# DWM1000Breakout.net
KiCad netlist of a schematic drawn in Altium Designer
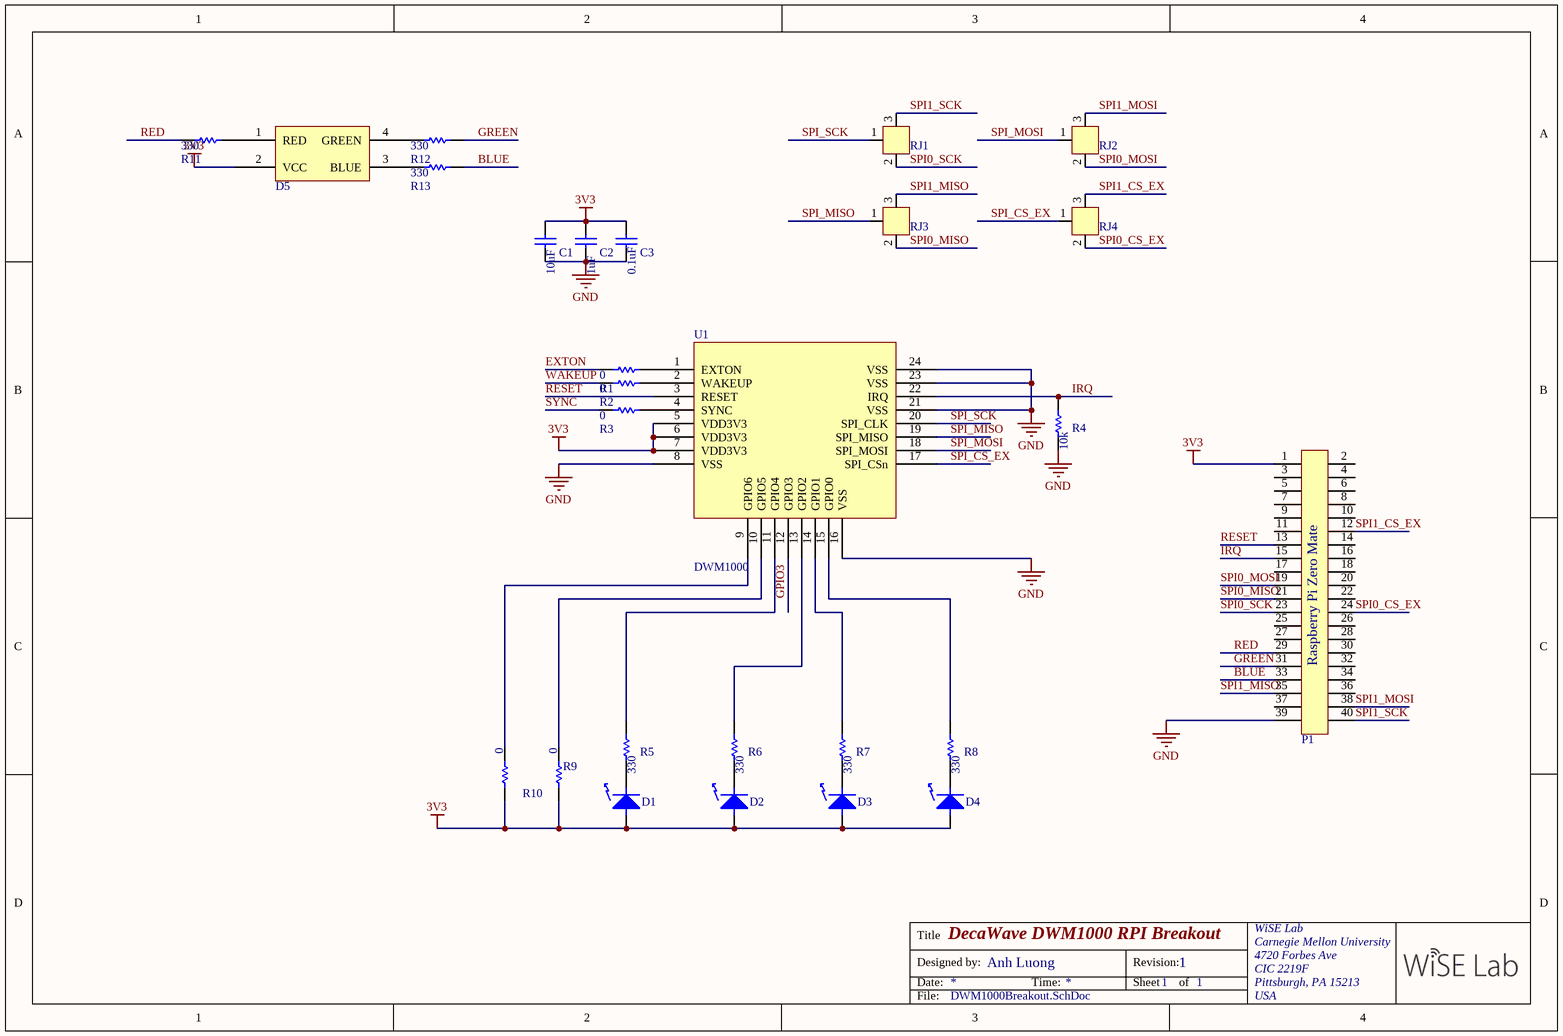
[diagram p0: DWM1000Breakout.SchDoc]

(export (version "E")
  (design (tool "Eeschema 10.0.6"))
  (components
    (comp (ref "C1")
      (value "GRM188R60J106ME47D")
      (footprint "CAPC1608X08N (0603)")
      (description "CAP CER 10UF 6.3V 20% X5R 0603")
      (fields
        (field (name "MANUFACTURER") "Murata Electronics North America")
        (field (name "TOLERANCE") "±20%")
      )
      (libsource (lib "DWM1000Breakout") (part "GRM188R60J106ME47D"))
    )
    (comp (ref "C2")
      (value "GRM188R61A105KA61D")
      (footprint "CAPC1608X08N (0603)")
      (description "CAP CER 1UF 10V 10% X5R 0603")
      (fields
        (field (name "MANUFACTURER") "Murata Electronics North America")
        (field (name "TOLERANCE") "±10%")
      )
      (libsource (lib "DWM1000Breakout") (part "GRM188R61A105KA61D"))
    )
    (comp (ref "C3")
      (value "GRM188R71C104KA01D")
      (footprint "CAPC1608X08N (0603)")
      (description "CAP CER 0.1UF 16V 10% X7R 0603")
      (fields
        (field (name "MANUFACTURER") "Murata Electronics North America")
        (field (name "TOLERANCE") "±10%")
      )
      (libsource (lib "DWM1000Breakout") (part "GRM188R71C104KA01D"))
    )
    (comp (ref "D1")
      (value "LG Q971-KN-1")
      (footprint "CHIPLED0603")
      (description "LED CHIPLED 570NM GREEN 0603 SMD")
      (fields (field (name "MANUFACTURER") "OSRAM Opto Semiconductors Inc"))
      (libsource (lib "DWM1000Breakout") (part "LG Q971-KN-1"))
    )
    (comp (ref "D2")
      (value "LG Q971-KN-1")
      (footprint "CHIPLED0603")
      (description "LED CHIPLED 570NM GREEN 0603 SMD")
      (fields (field (name "MANUFACTURER") "OSRAM Opto Semiconductors Inc"))
      (libsource (lib "DWM1000Breakout") (part "LG Q971-KN-1"))
    )
    (comp (ref "D3")
      (value "LG Q971-KN-1")
      (footprint "CHIPLED0603")
      (description "LED CHIPLED 570NM GREEN 0603 SMD")
      (fields (field (name "MANUFACTURER") "OSRAM Opto Semiconductors Inc"))
      (libsource (lib "DWM1000Breakout") (part "LG Q971-KN-1"))
    )
    (comp (ref "D4")
      (value "LG Q971-KN-1")
      (footprint "CHIPLED0603")
      (description "LED CHIPLED 570NM GREEN 0603 SMD")
      (fields (field (name "MANUFACTURER") "OSRAM Opto Semiconductors Inc"))
      (libsource (lib "DWM1000Breakout") (part "LG Q971-KN-1"))
    )
    (comp (ref "D5")
      (value "CLV1A-FKB-CJ1M1F1BB7R4S3")
      (footprint "CREE LV1")
      (description "LED RED/GREEN/BLUE PLCC4 SMD")
      (fields (field (name "MANUFACTURER") "Cree Inc"))
      (libsource (lib "Passives") (part "CLV1A-FKB-CJ1M1F1BB7R4S3"))
    )
    (comp (ref "P1")
      (value "Raspbery Pi Zero Mate")
      (footprint "Raspberry Pi Zero")
      (description "The header and mechanical drawings for connnecting a Raspbery Pi Zero")
      (libsource (lib "Connectors") (part "Raspberry Pi Zero Mate"))
    )
    (comp (ref "R1")
      (value "MCR03ERTJ000")
      (footprint "RESC1608X06N (0603)")
      (description "RES 0.0 OHM 1/10W JUMP 0603 SMD")
      (fields (field (name "MANUFACTURER") "Rohm Semiconductor") (field (name "TOLERANCE") "Jumper"))
      (libsource (lib "DWM1000Breakout") (part "MCR03ERTJ000"))
    )
    (comp (ref "R2")
      (value "MCR03ERTJ000")
      (footprint "RESC1608X06N (0603)")
      (description "RES 0.0 OHM 1/10W JUMP 0603 SMD")
      (fields (field (name "MANUFACTURER") "Rohm Semiconductor") (field (name "TOLERANCE") "Jumper"))
      (libsource (lib "DWM1000Breakout") (part "MCR03ERTJ000"))
    )
    (comp (ref "R3")
      (value "MCR03ERTJ000")
      (footprint "RESC1608X06N (0603)")
      (description "RES 0.0 OHM 1/10W JUMP 0603 SMD")
      (fields (field (name "MANUFACTURER") "Rohm Semiconductor") (field (name "TOLERANCE") "Jumper"))
      (libsource (lib "DWM1000Breakout") (part "MCR03ERTJ000"))
    )
    (comp (ref "R4")
      (value "MCR03ERTJ103")
      (footprint "RESC1608X06N (0603)")
      (description "RES 10K OHM 1/10W 5% 0603 SMD")
      (fields (field (name "MANUFACTURER") "Rohm Semiconductor") (field (name "TOLERANCE") "±5%"))
      (libsource (lib "DWM1000Breakout") (part "MCR03ERTJ103"))
    )
    (comp (ref "R5")
      (value "MCR03ERTJ331")
      (footprint "RESC1608X06N (0603)")
      (description "RES 330 OHM 1/10W 5% 0603 SMD")
      (fields (field (name "MANUFACTURER") "Rohm Semiconductor") (field (name "TOLERANCE") "±5%"))
      (libsource (lib "Passives") (part "MCR03ERTJ331"))
    )
    (comp (ref "R6")
      (value "MCR03ERTJ331")
      (footprint "RESC1608X06N (0603)")
      (description "RES 330 OHM 1/10W 5% 0603 SMD")
      (fields (field (name "MANUFACTURER") "Rohm Semiconductor") (field (name "TOLERANCE") "±5%"))
      (libsource (lib "Passives") (part "MCR03ERTJ331"))
    )
    (comp (ref "R7")
      (value "MCR03ERTJ331")
      (footprint "RESC1608X06N (0603)")
      (description "RES 330 OHM 1/10W 5% 0603 SMD")
      (fields (field (name "MANUFACTURER") "Rohm Semiconductor") (field (name "TOLERANCE") "±5%"))
      (libsource (lib "Passives") (part "MCR03ERTJ331"))
    )
    (comp (ref "R8")
      (value "MCR03ERTJ331")
      (footprint "RESC1608X06N (0603)")
      (description "RES 330 OHM 1/10W 5% 0603 SMD")
      (fields (field (name "MANUFACTURER") "Rohm Semiconductor") (field (name "TOLERANCE") "±5%"))
      (libsource (lib "Passives") (part "MCR03ERTJ331"))
    )
    (comp (ref "R9")
      (value "MCR03ERTJ000")
      (footprint "RESC1608X06N (0603)")
      (description "RES 0.0 OHM 1/10W JUMP 0603 SMD")
      (fields (field (name "MANUFACTURER") "Rohm Semiconductor") (field (name "TOLERANCE") "Jumper"))
      (libsource (lib "DWM1000Breakout") (part "MCR03ERTJ000"))
    )
    (comp (ref "R10")
      (value "MCR03ERTJ000")
      (footprint "RESC1608X06N (0603)")
      (description "RES 0.0 OHM 1/10W JUMP 0603 SMD")
      (fields (field (name "MANUFACTURER") "Rohm Semiconductor") (field (name "TOLERANCE") "Jumper"))
      (libsource (lib "DWM1000Breakout") (part "MCR03ERTJ000"))
    )
    (comp (ref "R11")
      (value "MCR03ERTJ331")
      (footprint "RESC1608X06N (0603)")
      (description "RES 330 OHM 1/10W 5% 0603 SMD")
      (fields (field (name "MANUFACTURER") "Rohm Semiconductor") (field (name "TOLERANCE") "±5%"))
      (libsource (lib "Passives") (part "MCR03ERTJ331"))
    )
    (comp (ref "R12")
      (value "MCR03ERTJ331")
      (footprint "RESC1608X06N (0603)")
      (description "RES 330 OHM 1/10W 5% 0603 SMD")
      (fields (field (name "MANUFACTURER") "Rohm Semiconductor") (field (name "TOLERANCE") "±5%"))
      (libsource (lib "Passives") (part "MCR03ERTJ331"))
    )
    (comp (ref "R13")
      (value "MCR03ERTJ331")
      (footprint "RESC1608X06N (0603)")
      (description "RES 330 OHM 1/10W 5% 0603 SMD")
      (fields (field (name "MANUFACTURER") "Rohm Semiconductor") (field (name "TOLERANCE") "±5%"))
      (libsource (lib "Passives") (part "MCR03ERTJ331"))
    )
    (comp (ref "RJ1")
      (value "R_J")
      (footprint "RJ")
      (description "Resistor Jumper")
      (libsource (lib "DWM1000Breakout") (part "R_J"))
    )
    (comp (ref "RJ2")
      (value "R_J")
      (footprint "RJ")
      (description "Resistor Jumper")
      (libsource (lib "DWM1000Breakout") (part "R_J"))
    )
    (comp (ref "RJ3")
      (value "R_J")
      (footprint "RJ")
      (description "Resistor Jumper")
      (libsource (lib "DWM1000Breakout") (part "R_J"))
    )
    (comp (ref "RJ4")
      (value "R_J")
      (footprint "RJ")
      (description "Resistor Jumper")
      (libsource (lib "DWM1000Breakout") (part "R_J"))
    )
    (comp (ref "U1")
      (value "DWM1000")
      (footprint "DWM1000")
      (description "MOD IEEE802.15.4-2011 UWB TXRX")
      (fields (field (name "MANUFACTURER") "Decawave Limited"))
      (libsource (lib "DWM1000Breakout") (part "DWM1000"))
    )
  )
  (nets
    (net (code "1") (name "/BLUE") (class "Default")
      (node (ref "P1") (pin "33") (pintype "passive"))
      (node (ref "R13") (pin "2") (pinfunction "2_2") (pintype "passive"))
    )
    (net (code "2") (name "/EXTON") (class "Default")
      (node (ref "R1") (pin "1") (pinfunction "1_1") (pintype "passive"))
    )
    (net (code "3") (name "/GPIO3") (class "Default")
      (node (ref "U1") (pin "12") (pinfunction "GPIO3_12") (pintype "passive"))
    )
    (net (code "4") (name "/GREEN") (class "Default")
      (node (ref "P1") (pin "31") (pintype "passive"))
      (node (ref "R12") (pin "2") (pinfunction "2_2") (pintype "passive"))
    )
    (net (code "5") (name "/IRQ") (class "Default")
      (node (ref "P1") (pin "15") (pintype "passive"))
      (node (ref "R4") (pin "2") (pinfunction "2_2") (pintype "passive"))
      (node (ref "U1") (pin "22") (pinfunction "IRQ_22") (pintype "passive"))
    )
    (net (code "6") (name "/RED") (class "Default")
      (node (ref "P1") (pin "29") (pintype "passive"))
      (node (ref "R11") (pin "1") (pinfunction "1_1") (pintype "passive"))
    )
    (net (code "7") (name "/RESET") (class "Default")
      (node (ref "P1") (pin "13") (pintype "passive"))
      (node (ref "U1") (pin "3") (pinfunction "RESET_3") (pintype "passive"))
    )
    (net (code "8") (name "/SPI0_CS_EX") (class "Default")
      (node (ref "P1") (pin "24") (pintype "passive"))
      (node (ref "RJ4") (pin "2") (pinfunction "2_2") (pintype "passive"))
    )
    (net (code "9") (name "/SPI0_MISO") (class "Default")
      (node (ref "P1") (pin "21") (pintype "passive"))
      (node (ref "RJ3") (pin "2") (pinfunction "2_2") (pintype "passive"))
    )
    (net (code "10") (name "/SPI0_MOSI") (class "Default")
      (node (ref "P1") (pin "19") (pintype "passive"))
      (node (ref "RJ2") (pin "2") (pinfunction "2_2") (pintype "passive"))
    )
    (net (code "11") (name "/SPI0_SCK") (class "Default")
      (node (ref "P1") (pin "23") (pintype "passive"))
      (node (ref "RJ1") (pin "2") (pinfunction "2_2") (pintype "passive"))
    )
    (net (code "12") (name "/SPI1_CS_EX") (class "Default")
      (node (ref "P1") (pin "12") (pintype "passive"))
      (node (ref "RJ4") (pin "3") (pinfunction "3_3") (pintype "passive"))
    )
    (net (code "13") (name "/SPI1_MISO") (class "Default")
      (node (ref "P1") (pin "35") (pintype "passive"))
      (node (ref "RJ3") (pin "3") (pinfunction "3_3") (pintype "passive"))
    )
    (net (code "14") (name "/SPI1_MOSI") (class "Default")
      (node (ref "P1") (pin "38") (pintype "passive"))
      (node (ref "RJ2") (pin "3") (pinfunction "3_3") (pintype "passive"))
    )
    (net (code "15") (name "/SPI1_SCK") (class "Default")
      (node (ref "P1") (pin "40") (pintype "passive"))
      (node (ref "RJ1") (pin "3") (pinfunction "3_3") (pintype "passive"))
    )
    (net (code "16") (name "/SPI_CS_EX") (class "Default")
      (node (ref "RJ4") (pin "1") (pinfunction "1_1") (pintype "passive"))
      (node (ref "U1") (pin "17") (pinfunction "SPI_CSn_17") (pintype "passive"))
    )
    (net (code "17") (name "/SPI_MISO") (class "Default")
      (node (ref "RJ3") (pin "1") (pinfunction "1_1") (pintype "passive"))
      (node (ref "U1") (pin "19") (pinfunction "SPI_MISO_19") (pintype "passive"))
    )
    (net (code "18") (name "/SPI_MOSI") (class "Default")
      (node (ref "RJ2") (pin "1") (pinfunction "1_1") (pintype "passive"))
      (node (ref "U1") (pin "18") (pinfunction "SPI_MOSI_18") (pintype "passive"))
    )
    (net (code "19") (name "/SPI_SCK") (class "Default")
      (node (ref "RJ1") (pin "1") (pinfunction "1_1") (pintype "passive"))
      (node (ref "U1") (pin "20") (pinfunction "SPI_CLK_20") (pintype "passive"))
    )
    (net (code "20") (name "/SYNC") (class "Default")
      (node (ref "R3") (pin "1") (pinfunction "1_1") (pintype "passive"))
    )
    (net (code "21") (name "/WAKEUP") (class "Default")
      (node (ref "R2") (pin "1") (pinfunction "1_1") (pintype "passive"))
    )
    (net (code "22") (name "3V3") (class "Default")
      (node (ref "C1") (pin "2") (pinfunction "2_2") (pintype "passive"))
      (node (ref "C2") (pin "2") (pinfunction "2_2") (pintype "passive"))
      (node (ref "C3") (pin "2") (pinfunction "2_2") (pintype "passive"))
      (node (ref "D1") (pin "1") (pinfunction "1_1") (pintype "passive"))
      (node (ref "D2") (pin "1") (pinfunction "1_1") (pintype "passive"))
      (node (ref "D3") (pin "1") (pinfunction "1_1") (pintype "passive"))
      (node (ref "D4") (pin "1") (pinfunction "1_1") (pintype "passive"))
      (node (ref "D5") (pin "2") (pinfunction "VCC_2") (pintype "passive"))
      (node (ref "P1") (pin "1") (pintype "passive"))
      (node (ref "R10") (pin "2") (pinfunction "2_2") (pintype "passive"))
      (node (ref "R9") (pin "2") (pinfunction "2_2") (pintype "passive"))
      (node (ref "U1") (pin "5") (pinfunction "VDD3V3_5") (pintype "passive"))
      (node (ref "U1") (pin "6") (pinfunction "VDD3V3_6") (pintype "passive"))
      (node (ref "U1") (pin "7") (pinfunction "VDD3V3_7") (pintype "passive"))
    )
    (net (code "23") (name "GND") (class "Default")
      (node (ref "C1") (pin "1") (pinfunction "1_1") (pintype "passive"))
      (node (ref "C2") (pin "1") (pinfunction "1_1") (pintype "passive"))
      (node (ref "C3") (pin "1") (pinfunction "1_1") (pintype "passive"))
      (node (ref "P1") (pin "39") (pintype "passive"))
      (node (ref "R4") (pin "1") (pinfunction "1_1") (pintype "passive"))
      (node (ref "U1") (pin "16") (pinfunction "VSS_16") (pintype "passive"))
      (node (ref "U1") (pin "21") (pinfunction "VSS_21") (pintype "passive"))
      (node (ref "U1") (pin "23") (pinfunction "VSS_23") (pintype "passive"))
      (node (ref "U1") (pin "24") (pinfunction "VSS_24") (pintype "passive"))
      (node (ref "U1") (pin "8") (pinfunction "VSS_8") (pintype "passive"))
    )
    (net (code "24") (name "Net-(D1-Pad2)") (class "Default")
      (node (ref "D1") (pin "2") (pinfunction "2_2") (pintype "passive"))
      (node (ref "R5") (pin "1") (pinfunction "1_1") (pintype "passive"))
    )
    (net (code "25") (name "Net-(D2-Pad2)") (class "Default")
      (node (ref "D2") (pin "2") (pinfunction "2_2") (pintype "passive"))
      (node (ref "R6") (pin "1") (pinfunction "1_1") (pintype "passive"))
    )
    (net (code "26") (name "Net-(D3-Pad2)") (class "Default")
      (node (ref "D3") (pin "2") (pinfunction "2_2") (pintype "passive"))
      (node (ref "R7") (pin "1") (pinfunction "1_1") (pintype "passive"))
    )
    (net (code "27") (name "Net-(D4-Pad2)") (class "Default")
      (node (ref "D4") (pin "2") (pinfunction "2_2") (pintype "passive"))
      (node (ref "R8") (pin "1") (pinfunction "1_1") (pintype "passive"))
    )
    (net (code "28") (name "Net-(D5-BLUE)") (class "Default")
      (node (ref "D5") (pin "3") (pinfunction "BLUE_3") (pintype "passive"))
      (node (ref "R13") (pin "1") (pinfunction "1_1") (pintype "passive"))
    )
    (net (code "29") (name "Net-(D5-GREEN)") (class "Default")
      (node (ref "D5") (pin "4") (pinfunction "GREEN_4") (pintype "passive"))
      (node (ref "R12") (pin "1") (pinfunction "1_1") (pintype "passive"))
    )
    (net (code "30") (name "Net-(D5-RED)") (class "Default")
      (node (ref "D5") (pin "1") (pinfunction "RED_1") (pintype "passive"))
      (node (ref "R11") (pin "2") (pinfunction "2_2") (pintype "passive"))
    )
    (net (code "31") (name "Net-(U1-EXTON)") (class "Default")
      (node (ref "R1") (pin "2") (pinfunction "2_2") (pintype "passive"))
      (node (ref "U1") (pin "1") (pinfunction "EXTON_1") (pintype "passive"))
    )
    (net (code "32") (name "Net-(U1-GPIO0)") (class "Default")
      (node (ref "R8") (pin "2") (pinfunction "2_2") (pintype "passive"))
      (node (ref "U1") (pin "15") (pinfunction "GPIO0_15") (pintype "passive"))
    )
    (net (code "33") (name "Net-(U1-GPIO1)") (class "Default")
      (node (ref "R7") (pin "2") (pinfunction "2_2") (pintype "passive"))
      (node (ref "U1") (pin "14") (pinfunction "GPIO1_14") (pintype "passive"))
    )
    (net (code "34") (name "Net-(U1-GPIO2)") (class "Default")
      (node (ref "R6") (pin "2") (pinfunction "2_2") (pintype "passive"))
      (node (ref "U1") (pin "13") (pinfunction "GPIO2_13") (pintype "passive"))
    )
    (net (code "35") (name "Net-(U1-GPIO4)") (class "Default")
      (node (ref "R5") (pin "2") (pinfunction "2_2") (pintype "passive"))
      (node (ref "U1") (pin "11") (pinfunction "GPIO4_11") (pintype "passive"))
    )
    (net (code "36") (name "Net-(U1-GPIO5)") (class "Default")
      (node (ref "R9") (pin "1") (pinfunction "1_1") (pintype "passive"))
      (node (ref "U1") (pin "10") (pinfunction "GPIO5_10") (pintype "passive"))
    )
    (net (code "37") (name "Net-(U1-GPIO6)") (class "Default")
      (node (ref "R10") (pin "1") (pinfunction "1_1") (pintype "passive"))
      (node (ref "U1") (pin "9") (pinfunction "GPIO6_9") (pintype "passive"))
    )
    (net (code "38") (name "Net-(U1-SYNC)") (class "Default")
      (node (ref "R3") (pin "2") (pinfunction "2_2") (pintype "passive"))
      (node (ref "U1") (pin "4") (pinfunction "SYNC_4") (pintype "passive"))
    )
    (net (code "39") (name "Net-(U1-WAKEUP)") (class "Default")
      (node (ref "R2") (pin "2") (pinfunction "2_2") (pintype "passive"))
      (node (ref "U1") (pin "2") (pinfunction "WAKEUP_2") (pintype "passive"))
    )
    (net (code "40") (name "unconnected-(P1-Pad2)") (class "Default")
      (node (ref "P1") (pin "2") (pintype "passive"))
    )
    (net (code "41") (name "unconnected-(P1-Pad3)") (class "Default")
      (node (ref "P1") (pin "3") (pintype "passive"))
    )
    (net (code "42") (name "unconnected-(P1-Pad4)") (class "Default")
      (node (ref "P1") (pin "4") (pintype "passive"))
    )
    (net (code "43") (name "unconnected-(P1-Pad5)") (class "Default")
      (node (ref "P1") (pin "5") (pintype "passive"))
    )
    (net (code "44") (name "unconnected-(P1-Pad6)") (class "Default")
      (node (ref "P1") (pin "6") (pintype "passive"))
    )
    (net (code "45") (name "unconnected-(P1-Pad7)") (class "Default")
      (node (ref "P1") (pin "7") (pintype "passive"))
    )
    (net (code "46") (name "unconnected-(P1-Pad8)") (class "Default")
      (node (ref "P1") (pin "8") (pintype "passive"))
    )
    (net (code "47") (name "unconnected-(P1-Pad9)") (class "Default")
      (node (ref "P1") (pin "9") (pintype "passive"))
    )
    (net (code "48") (name "unconnected-(P1-Pad10)") (class "Default")
      (node (ref "P1") (pin "10") (pintype "passive"))
    )
    (net (code "49") (name "unconnected-(P1-Pad11)") (class "Default")
      (node (ref "P1") (pin "11") (pintype "passive"))
    )
    (net (code "50") (name "unconnected-(P1-Pad14)") (class "Default")
      (node (ref "P1") (pin "14") (pintype "passive"))
    )
    (net (code "51") (name "unconnected-(P1-Pad16)") (class "Default")
      (node (ref "P1") (pin "16") (pintype "passive"))
    )
    (net (code "52") (name "unconnected-(P1-Pad17)") (class "Default")
      (node (ref "P1") (pin "17") (pintype "passive"))
    )
    (net (code "53") (name "unconnected-(P1-Pad18)") (class "Default")
      (node (ref "P1") (pin "18") (pintype "passive"))
    )
    (net (code "54") (name "unconnected-(P1-Pad20)") (class "Default")
      (node (ref "P1") (pin "20") (pintype "passive"))
    )
    (net (code "55") (name "unconnected-(P1-Pad22)") (class "Default")
      (node (ref "P1") (pin "22") (pintype "passive"))
    )
    (net (code "56") (name "unconnected-(P1-Pad25)") (class "Default")
      (node (ref "P1") (pin "25") (pintype "passive"))
    )
    (net (code "57") (name "unconnected-(P1-Pad26)") (class "Default")
      (node (ref "P1") (pin "26") (pintype "passive"))
    )
    (net (code "58") (name "unconnected-(P1-Pad27)") (class "Default")
      (node (ref "P1") (pin "27") (pintype "passive"))
    )
    (net (code "59") (name "unconnected-(P1-Pad28)") (class "Default")
      (node (ref "P1") (pin "28") (pintype "passive"))
    )
    (net (code "60") (name "unconnected-(P1-Pad30)") (class "Default")
      (node (ref "P1") (pin "30") (pintype "passive"))
    )
    (net (code "61") (name "unconnected-(P1-Pad32)") (class "Default")
      (node (ref "P1") (pin "32") (pintype "passive"))
    )
    (net (code "62") (name "unconnected-(P1-Pad34)") (class "Default")
      (node (ref "P1") (pin "34") (pintype "passive"))
    )
    (net (code "63") (name "unconnected-(P1-Pad36)") (class "Default")
      (node (ref "P1") (pin "36") (pintype "passive"))
    )
    (net (code "64") (name "unconnected-(P1-Pad37)") (class "Default")
      (node (ref "P1") (pin "37") (pintype "passive"))
    )
  )
)
